# qtpy_synth2a.net
KiCad netlist of a schematic drawn in EAGLE
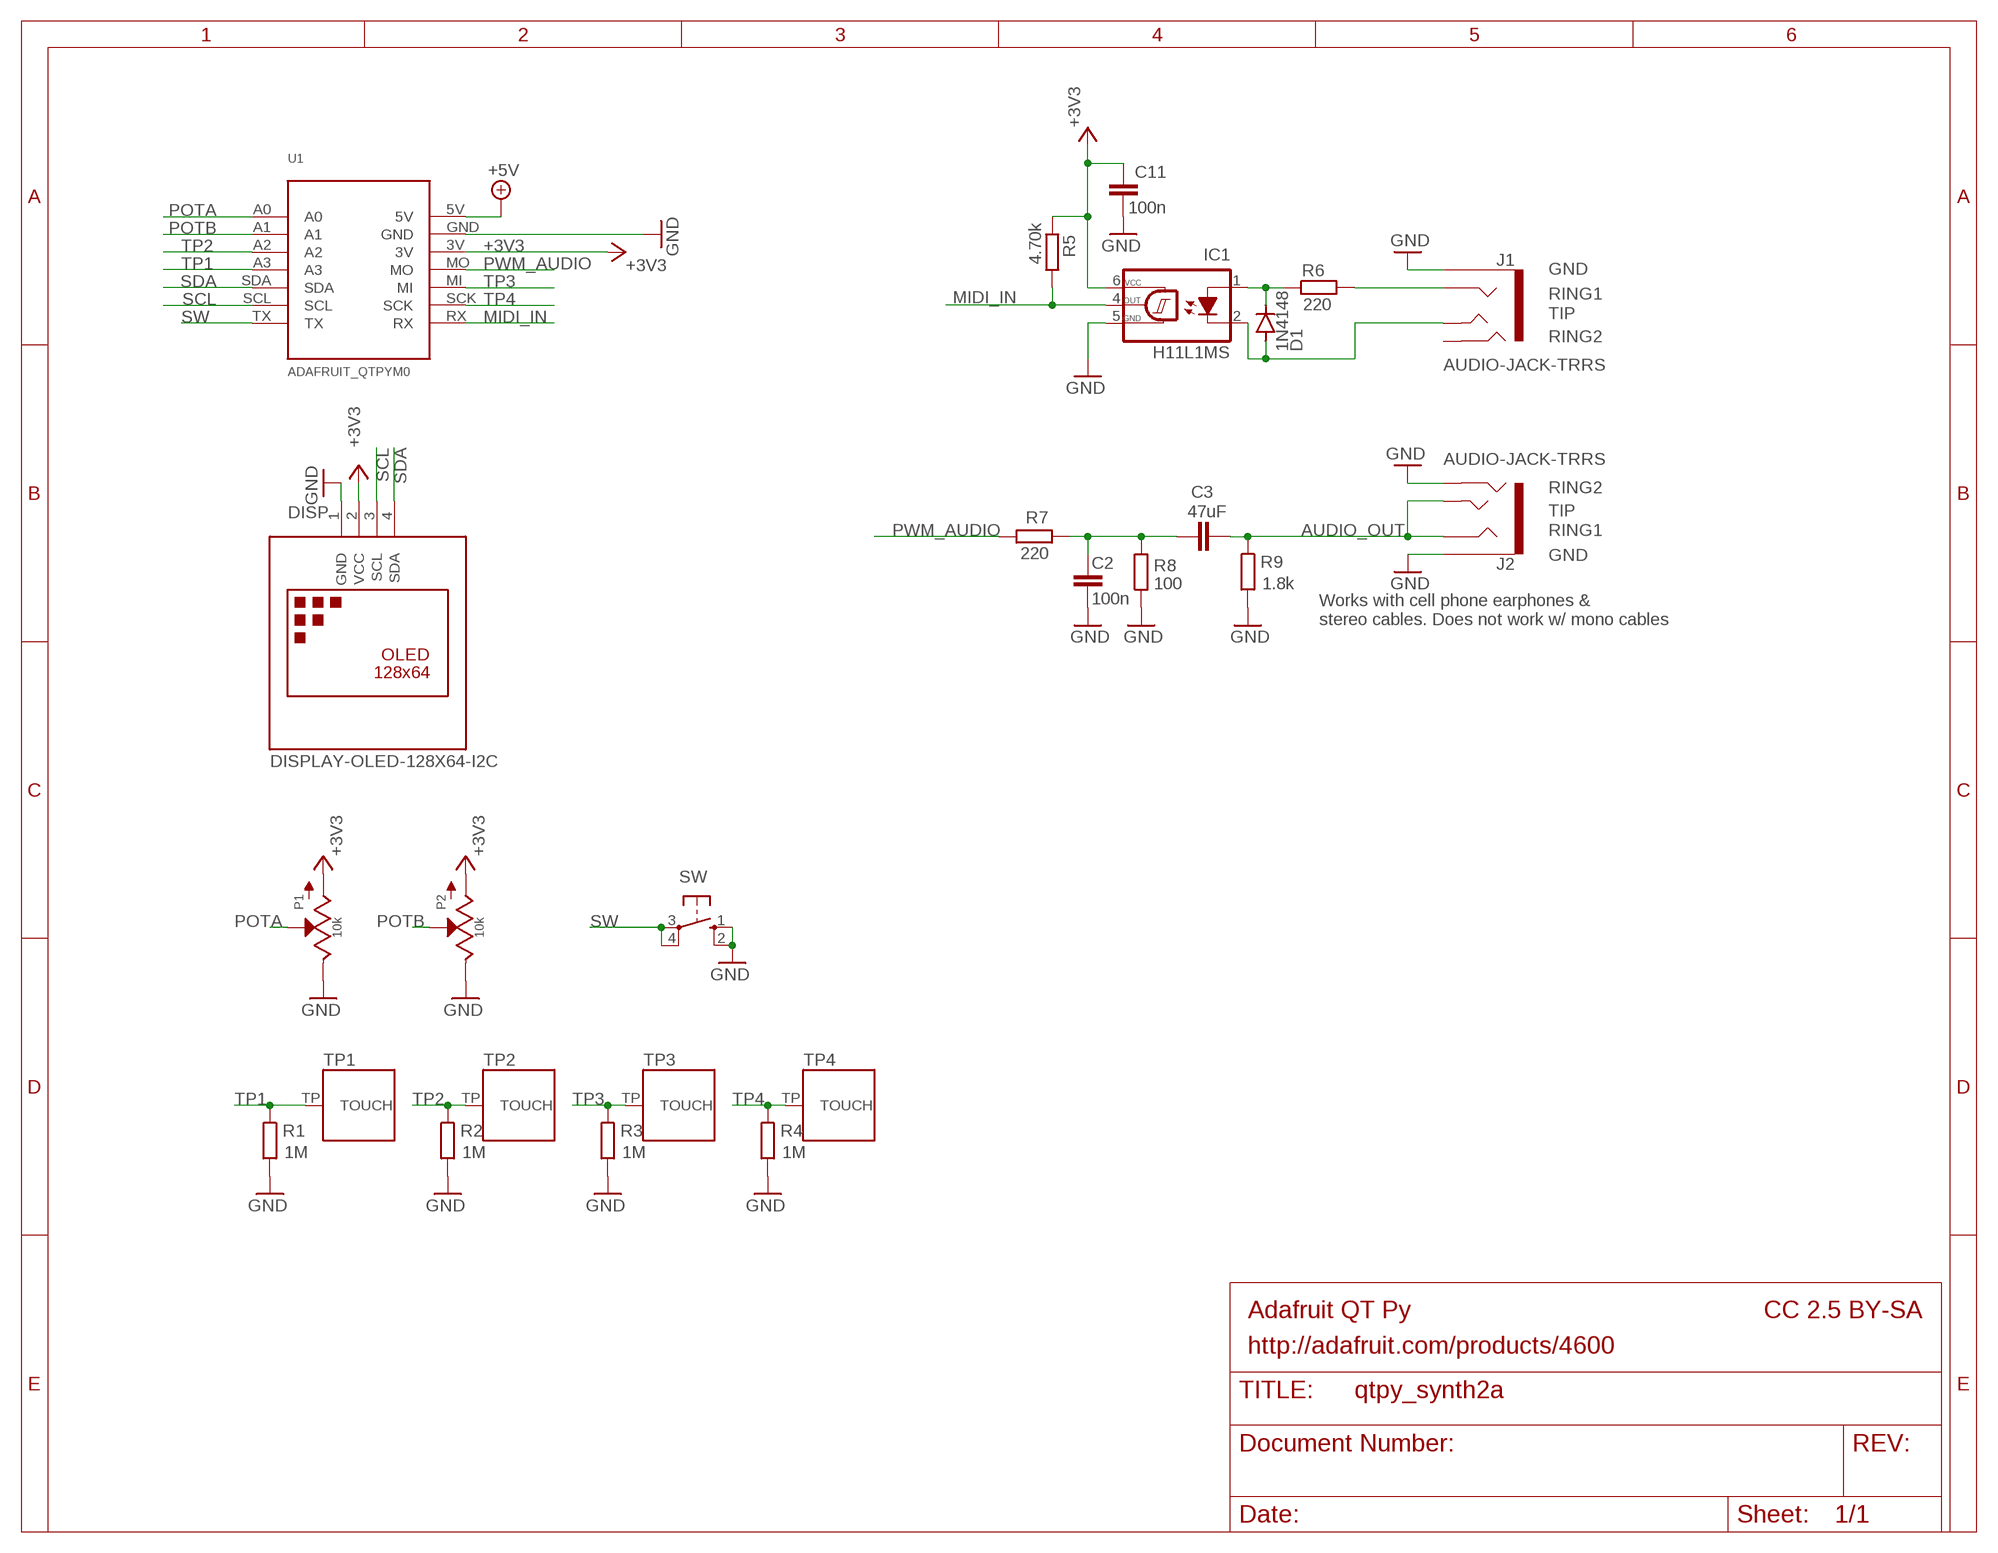
[diagram p0: schematic, sheet 1]

(export (version "E")
  (design (tool "Eeschema 10.0.6"))
  (components
    (comp (ref "C2")
      (value "100n")
      (footprint "eagle-import:C0805")
      (libsource (lib "eagle-import") (part "C-EUC0805"))
    )
    (comp (ref "C3")
      (value "47uF")
      (footprint "eagle-import:C0805")
      (libsource (lib "eagle-import") (part "C-EUC0805"))
    )
    (comp (ref "C11")
      (value "100n")
      (footprint "eagle-import:C0805")
      (libsource (lib "eagle-import") (part "C-EUC0805"))
    )
    (comp (ref "D1")
      (value "1N4148")
      (footprint "eagle-import:SOD123")
      (libsource (lib "eagle-import") (part "DIODE-SOD123"))
    )
    (comp (ref "DISP")
      (value "DISPLAY-OLED-128X64-I2C")
      (footprint "eagle-import:DISPLAY-OLED-128X64-I2C")
      (libsource (lib "eagle-import") (part "DISPLAY-OLED-128X64-I2C"))
    )
    (comp (ref "IC1")
      (value "H11L1MS")
      (footprint "eagle-import:DIL6-SMD")
      (libsource (lib "eagle-import") (part "H11LMS1"))
    )
    (comp (ref "J1")
      (value "AUDIO-JACK-TRRS")
      (footprint "eagle-import:PJ-320D_SPARKFUN")
      (fields (field (name "MPN") "PJ-320D"))
      (libsource (lib "eagle-import") (part "AUDIO-JACK-TRRS"))
    )
    (comp (ref "J2")
      (value "AUDIO-JACK-TRRS")
      (footprint "eagle-import:PJ-320D_SPARKFUN")
      (fields (field (name "MPN") "PJ-320D") (field (name "LCSC") "C431535"))
      (libsource (lib "eagle-import") (part "AUDIO-JACK-TRRS"))
    )
    (comp (ref "P1")
      (value "10k")
      (footprint "eagle-import:OG-POTS_ALPS_POT_VERTICAL_WITHBIGKNOB")
      (libsource (lib "eagle-import") (part "POTZEPHPOT_BIGKNOB"))
    )
    (comp (ref "P2")
      (value "10k")
      (footprint "eagle-import:OG-POTS_ALPS_POT_VERTICAL_WITHBIGKNOB")
      (libsource (lib "eagle-import") (part "POTZEPHPOT_BIGKNOB"))
    )
    (comp (ref "R1")
      (value "1M")
      (footprint "eagle-import:R0805")
      (libsource (lib "eagle-import") (part "R-EU_R0805"))
    )
    (comp (ref "R2")
      (value "1M")
      (footprint "eagle-import:R0805")
      (libsource (lib "eagle-import") (part "R-EU_R0805"))
    )
    (comp (ref "R3")
      (value "1M")
      (footprint "eagle-import:R0805")
      (libsource (lib "eagle-import") (part "R-EU_R0805"))
    )
    (comp (ref "R4")
      (value "1M")
      (footprint "eagle-import:R0805")
      (libsource (lib "eagle-import") (part "R-EU_R0805"))
    )
    (comp (ref "R5")
      (value "4.70k")
      (footprint "eagle-import:R0805")
      (libsource (lib "eagle-import") (part "R-EU_R0805"))
    )
    (comp (ref "R6")
      (value "220")
      (footprint "eagle-import:R0805")
      (libsource (lib "eagle-import") (part "R-EU_R0805"))
    )
    (comp (ref "R7")
      (value "220")
      (footprint "eagle-import:R0805")
      (libsource (lib "eagle-import") (part "R-EU_R0805"))
    )
    (comp (ref "R8")
      (value "100")
      (footprint "eagle-import:R0805")
      (libsource (lib "eagle-import") (part "R-EU_R0805"))
    )
    (comp (ref "R9")
      (value "1.8k")
      (footprint "eagle-import:R0805")
      (libsource (lib "eagle-import") (part "R-EU_R0805"))
    )
    (comp (ref "SW")
      (value "10-XX")
      (footprint "eagle-import:B3F-10XX")
      (fields (field (name "MPN") "B3F-1000"))
      (libsource (lib "eagle-import") (part "10-XX"))
    )
    (comp (ref "TP1")
      (value "TOUCHPADA")
      (footprint "eagle-import:TOUCHPADA_0.5IN")
      (libsource (lib "eagle-import") (part "TOUCHPADA"))
    )
    (comp (ref "TP2")
      (value "TOUCHPADA")
      (footprint "eagle-import:TOUCHPADA_0.5IN")
      (libsource (lib "eagle-import") (part "TOUCHPADA"))
    )
    (comp (ref "TP3")
      (value "TOUCHPADA")
      (footprint "eagle-import:TOUCHPADA_0.5IN")
      (libsource (lib "eagle-import") (part "TOUCHPADA"))
    )
    (comp (ref "TP4")
      (value "TOUCHPADA")
      (footprint "eagle-import:TOUCHPADA_0.5IN")
      (libsource (lib "eagle-import") (part "TOUCHPADA"))
    )
    (comp (ref "U1")
      (value "ADAFRUIT_QTPYM0")
      (footprint "eagle-import:ADAFRUIT_QTPY_M0")
      (libsource (lib "eagle-import") (part "ADAFRUIT_QTPYM0"))
    )
  )
  (nets
    (net (code "1") (name "+3V3") (class "Default")
      (node (ref "C11") (pin "1") (pinfunction "1_1") (pintype "passive"))
      (node (ref "DISP") (pin "2") (pinfunction "VCC_2") (pintype "power_in"))
      (node (ref "IC1") (pin "6") (pinfunction "VCC_6") (pintype "power_in"))
      (node (ref "P1") (pin "P$3") (pinfunction "A_P$3") (pintype "passive"))
      (node (ref "P2") (pin "P$3") (pinfunction "A_P$3") (pintype "passive"))
      (node (ref "R5") (pin "1") (pinfunction "1_1") (pintype "passive"))
      (node (ref "U1") (pin "3V") (pinfunction "3V_3V") (pintype "bidirectional"))
    )
    (net (code "2") (name "+5V") (class "Default")
      (node (ref "U1") (pin "5V") (pinfunction "5V_5V") (pintype "bidirectional"))
    )
    (net (code "3") (name "/AUDIO_OUT") (class "Default")
      (node (ref "C3") (pin "2") (pinfunction "2_2") (pintype "passive"))
      (node (ref "J2") (pin "RING1") (pinfunction "RING1_RING1") (pintype "bidirectional"))
      (node (ref "J2") (pin "TIP") (pinfunction "TIP_TIP") (pintype "bidirectional"))
      (node (ref "R9") (pin "1") (pinfunction "1_1") (pintype "passive"))
    )
    (net (code "4") (name "/MIDI_IN") (class "Default")
      (node (ref "IC1") (pin "4") (pinfunction "OUT_4") (pintype "output"))
      (node (ref "R5") (pin "2") (pinfunction "2_2") (pintype "passive"))
      (node (ref "U1") (pin "RX") (pinfunction "RX_RX") (pintype "bidirectional"))
    )
    (net (code "5") (name "/POTA") (class "Default")
      (node (ref "P1") (pin "P$2") (pinfunction "S_P$2") (pintype "passive"))
      (node (ref "U1") (pin "A0") (pinfunction "A0_A0") (pintype "bidirectional"))
    )
    (net (code "6") (name "/POTB") (class "Default")
      (node (ref "P2") (pin "P$2") (pinfunction "S_P$2") (pintype "passive"))
      (node (ref "U1") (pin "A1") (pinfunction "A1_A1") (pintype "bidirectional"))
    )
    (net (code "7") (name "/PWM_AUDIO") (class "Default")
      (node (ref "R7") (pin "2") (pinfunction "2_2") (pintype "passive"))
      (node (ref "U1") (pin "MO") (pinfunction "MO_MO") (pintype "bidirectional"))
    )
    (net (code "8") (name "/SCL") (class "Default")
      (node (ref "DISP") (pin "3") (pinfunction "SCL_3") (pintype "bidirectional"))
      (node (ref "U1") (pin "SCL") (pinfunction "SCL_SCL") (pintype "bidirectional"))
    )
    (net (code "9") (name "/SDA") (class "Default")
      (node (ref "DISP") (pin "4") (pinfunction "SDA_4") (pintype "bidirectional"))
      (node (ref "U1") (pin "SDA") (pinfunction "SDA_SDA") (pintype "bidirectional"))
    )
    (net (code "10") (name "/SW") (class "Default")
      (node (ref "SW") (pin "3") (pinfunction "P_3") (pintype "passive"))
      (node (ref "SW") (pin "4") (pinfunction "P1_4") (pintype "passive"))
      (node (ref "U1") (pin "TX") (pinfunction "TX_TX") (pintype "bidirectional"))
    )
    (net (code "11") (name "/TP1") (class "Default")
      (node (ref "R1") (pin "1") (pinfunction "1_1") (pintype "passive"))
      (node (ref "TP1") (pin "TP") (pinfunction "TOUCH_TP") (pintype "bidirectional"))
      (node (ref "U1") (pin "A3") (pinfunction "A3_A3") (pintype "bidirectional"))
    )
    (net (code "12") (name "/TP2") (class "Default")
      (node (ref "R2") (pin "1") (pinfunction "1_1") (pintype "passive"))
      (node (ref "TP2") (pin "TP") (pinfunction "TOUCH_TP") (pintype "bidirectional"))
      (node (ref "U1") (pin "A2") (pinfunction "A2_A2") (pintype "bidirectional"))
    )
    (net (code "13") (name "/TP3") (class "Default")
      (node (ref "R3") (pin "1") (pinfunction "1_1") (pintype "passive"))
      (node (ref "TP3") (pin "TP") (pinfunction "TOUCH_TP") (pintype "bidirectional"))
      (node (ref "U1") (pin "MI") (pinfunction "MI_MI") (pintype "bidirectional"))
    )
    (net (code "14") (name "/TP4") (class "Default")
      (node (ref "R4") (pin "1") (pinfunction "1_1") (pintype "passive"))
      (node (ref "TP4") (pin "TP") (pinfunction "TOUCH_TP") (pintype "bidirectional"))
      (node (ref "U1") (pin "SCK") (pinfunction "SCK_SCK") (pintype "bidirectional"))
    )
    (net (code "15") (name "GND") (class "Default")
      (node (ref "C11") (pin "2") (pinfunction "2_2") (pintype "passive"))
      (node (ref "C2") (pin "2") (pinfunction "2_2") (pintype "passive"))
      (node (ref "DISP") (pin "1") (pinfunction "GND_1") (pintype "power_in"))
      (node (ref "IC1") (pin "5") (pinfunction "GND_5") (pintype "power_in"))
      (node (ref "J1") (pin "EARTH") (pinfunction "EARTH_EARTH") (pintype "bidirectional"))
      (node (ref "J2") (pin "EARTH") (pinfunction "EARTH_EARTH") (pintype "bidirectional"))
      (node (ref "J2") (pin "RING2") (pinfunction "RING2_RING2") (pintype "bidirectional"))
      (node (ref "P1") (pin "P$1") (pinfunction "E_P$1") (pintype "passive"))
      (node (ref "P2") (pin "P$1") (pinfunction "E_P$1") (pintype "passive"))
      (node (ref "R1") (pin "2") (pinfunction "2_2") (pintype "passive"))
      (node (ref "R2") (pin "2") (pinfunction "2_2") (pintype "passive"))
      (node (ref "R3") (pin "2") (pinfunction "2_2") (pintype "passive"))
      (node (ref "R4") (pin "2") (pinfunction "2_2") (pintype "passive"))
      (node (ref "R8") (pin "1") (pinfunction "1_1") (pintype "passive"))
      (node (ref "R9") (pin "2") (pinfunction "2_2") (pintype "passive"))
      (node (ref "SW") (pin "1") (pinfunction "S_1") (pintype "passive"))
      (node (ref "SW") (pin "2") (pinfunction "S1_2") (pintype "passive"))
      (node (ref "U1") (pin "GND") (pinfunction "GND_GND") (pintype "bidirectional"))
    )
    (net (code "16") (name "Net-(C2-Pad1)") (class "Default")
      (node (ref "C2") (pin "1") (pinfunction "1_1") (pintype "passive"))
      (node (ref "C3") (pin "1") (pinfunction "1_1") (pintype "passive"))
      (node (ref "R7") (pin "1") (pinfunction "1_1") (pintype "passive"))
      (node (ref "R8") (pin "2") (pinfunction "2_2") (pintype "passive"))
    )
    (net (code "17") (name "Net-(IC1-A)") (class "Default")
      (node (ref "D1") (pin "C") (pinfunction "C_C") (pintype "passive"))
      (node (ref "IC1") (pin "1") (pinfunction "A_1") (pintype "passive"))
      (node (ref "R6") (pin "1") (pinfunction "1_1") (pintype "passive"))
    )
    (net (code "18") (name "Net-(IC1-C)") (class "Default")
      (node (ref "D1") (pin "A") (pinfunction "A_A") (pintype "passive"))
      (node (ref "IC1") (pin "2") (pinfunction "C_2") (pintype "passive"))
      (node (ref "J1") (pin "TIP") (pinfunction "TIP_TIP") (pintype "bidirectional"))
    )
    (net (code "19") (name "Net-(J1-PadRING1)") (class "Default")
      (node (ref "J1") (pin "RING1") (pinfunction "RING1_RING1") (pintype "bidirectional"))
      (node (ref "R6") (pin "2") (pinfunction "2_2") (pintype "passive"))
    )
    (net (code "20") (name "unconnected-(J1-PadRING2)") (class "Default")
      (node (ref "J1") (pin "RING2") (pinfunction "RING2_RING2") (pintype "bidirectional"))
    )
  )
)
